# motorplank.net
KiCad netlist of a schematic drawn in EAGLE
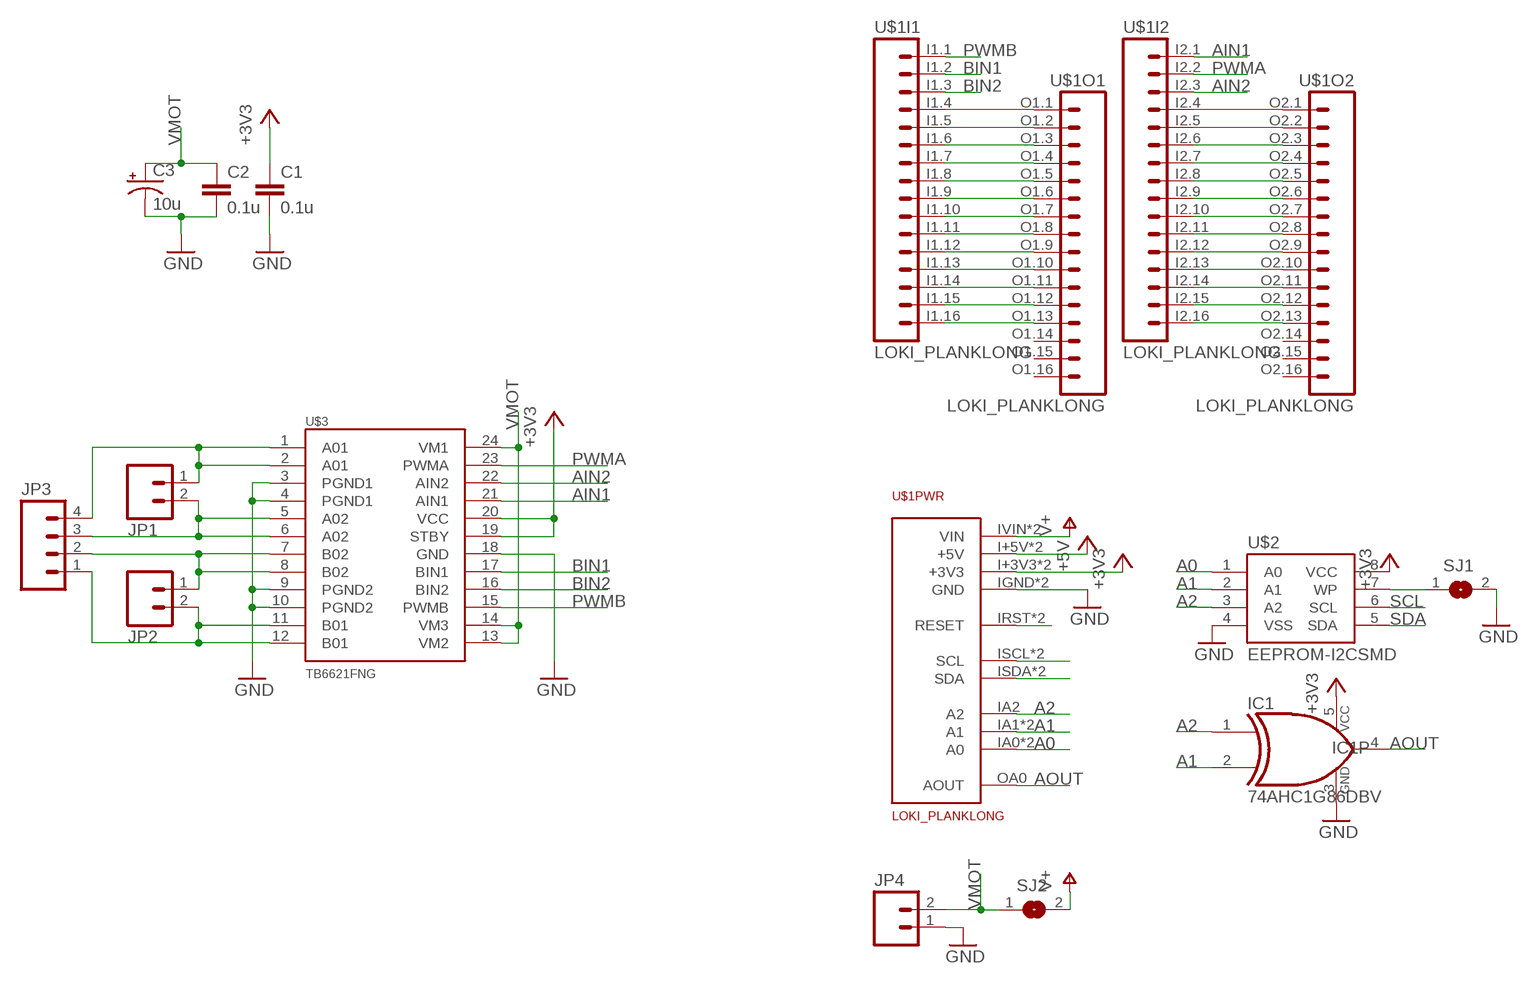
[diagram p0: schematic, sheet 1]

(export (version "E")
  (design (tool "Eeschema 10.0.6"))
  (components
    (comp (ref "C1")
      (value "0.1u")
      (footprint "eagle-import:0603-CAP")
      (libsource (lib "eagle-import") (part "CAP0603-CAP"))
    )
    (comp (ref "C2")
      (value "0.1u")
      (footprint "eagle-import:0603-CAP")
      (libsource (lib "eagle-import") (part "CAP0603-CAP"))
    )
    (comp (ref "C3")
      (value "10u")
      (footprint "eagle-import:PANASONIC_C")
      (libsource (lib "eagle-import") (part "CAP_POLC"))
    )
    (comp (ref "IC1")
      (value "74AHC1G86DBV")
      (footprint "eagle-import:SOT23-5")
      (libsource (lib "eagle-import") (part "741G86DBVAHC"))
    )
    (comp (ref "JP1")
      (value "M023.5MM")
      (footprint "eagle-import:SCREWTERMINAL-3.5MM-2")
      (libsource (lib "eagle-import") (part "M023.5MM"))
    )
    (comp (ref "JP2")
      (value "M023.5MM")
      (footprint "eagle-import:SCREWTERMINAL-3.5MM-2")
      (libsource (lib "eagle-import") (part "M023.5MM"))
    )
    (comp (ref "JP3")
      (value "M04PTH")
      (footprint "eagle-import:1X04")
      (libsource (lib "eagle-import") (part "M04PTH"))
    )
    (comp (ref "JP4")
      (value "M023.5MM")
      (footprint "eagle-import:SCREWTERMINAL-3.5MM-2")
      (libsource (lib "eagle-import") (part "M023.5MM"))
    )
    (comp (ref "SJ1") (value "SJ") (footprint "eagle-import:SJ") (libsource (lib "eagle-import") (part "SJ")))
    (comp (ref "SJ2") (value "SJ") (footprint "eagle-import:SJ") (libsource (lib "eagle-import") (part "SJ")))
    (comp (ref "U$1")
      (value "LOKI_PLANKLONG")
      (footprint "eagle-import:PLANK_LONG")
      (libsource (lib "eagle-import") (part "LOKI_PLANKLONG"))
    )
    (comp (ref "U$2")
      (value "EEPROM-I2CSMD")
      (footprint "eagle-import:SO08")
      (libsource (lib "eagle-import") (part "EEPROM-I2CSMD"))
    )
    (comp (ref "U$3")
      (value "TB6621FNG")
      (footprint "eagle-import:SSOP24")
      (libsource (lib "eagle-import") (part "TB6621FNG"))
    )
  )
  (nets
    (net (code "1") (name "+3V3") (class "Default")
      (node (ref "C1") (pin "1") (pinfunction "1_1") (pintype "passive"))
      (node (ref "IC1") (pin "5") (pinfunction "VCC_5") (pintype "power_in"))
      (node (ref "U$1") (pin "I+3V3") (pinfunction "+3V3_I+3V3") (pintype "power_in"))
      (node (ref "U$1") (pin "O+3V3") (pinfunction "+3V3_O+3V3") (pintype "power_in"))
      (node (ref "U$2") (pin "8") (pinfunction "VCC_8") (pintype "power_in"))
      (node (ref "U$3") (pin "19") (pinfunction "STBY_19") (pintype "bidirectional"))
      (node (ref "U$3") (pin "20") (pinfunction "VCC_20") (pintype "bidirectional"))
    )
    (net (code "2") (name "+5V") (class "Default")
      (node (ref "U$1") (pin "I+5V") (pinfunction "+5V_I+5V") (pintype "power_in"))
      (node (ref "U$1") (pin "O+5V") (pinfunction "+5V_O+5V") (pintype "power_in"))
    )
    (net (code "3") (name "/A0") (class "Default")
      (node (ref "U$1") (pin "IA0") (pinfunction "A0_IA0") (pintype "output"))
      (node (ref "U$1") (pin "OA1") (pinfunction "A0_OA1") (pintype "output"))
      (node (ref "U$2") (pin "1") (pinfunction "A0_1") (pintype "bidirectional"))
    )
    (net (code "4") (name "/A1") (class "Default")
      (node (ref "IC1") (pin "2") (pinfunction "I1_2") (pintype "input"))
      (node (ref "U$1") (pin "IA1") (pinfunction "A1_IA1") (pintype "output"))
      (node (ref "U$1") (pin "OA2") (pinfunction "A1_OA2") (pintype "output"))
      (node (ref "U$2") (pin "2") (pinfunction "A1_2") (pintype "bidirectional"))
    )
    (net (code "5") (name "/A2") (class "Default")
      (node (ref "IC1") (pin "1") (pinfunction "I0_1") (pintype "input"))
      (node (ref "U$1") (pin "IA2") (pinfunction "A2_IA2") (pintype "output"))
      (node (ref "U$2") (pin "3") (pinfunction "A2_3") (pintype "bidirectional"))
    )
    (net (code "6") (name "/AIN1") (class "Default")
      (node (ref "U$1") (pin "I2.1") (pinfunction "1_I2.1") (pintype "passive"))
      (node (ref "U$3") (pin "21") (pinfunction "AIN1_21") (pintype "bidirectional"))
    )
    (net (code "7") (name "/AIN2") (class "Default")
      (node (ref "U$1") (pin "I2.3") (pinfunction "3_I2.3") (pintype "passive"))
      (node (ref "U$3") (pin "22") (pinfunction "AIN2_22") (pintype "bidirectional"))
    )
    (net (code "8") (name "/AOUT") (class "Default")
      (node (ref "IC1") (pin "4") (pinfunction "O_4") (pintype "output"))
      (node (ref "U$1") (pin "OA0") (pinfunction "AOUT_OA0") (pintype "input"))
    )
    (net (code "9") (name "/BIN1") (class "Default")
      (node (ref "U$1") (pin "I1.2") (pinfunction "2_I1.2") (pintype "passive"))
      (node (ref "U$3") (pin "17") (pinfunction "BIN1_17") (pintype "bidirectional"))
    )
    (net (code "10") (name "/BIN2") (class "Default")
      (node (ref "U$1") (pin "I1.3") (pinfunction "3_I1.3") (pintype "passive"))
      (node (ref "U$3") (pin "16") (pinfunction "BIN2_16") (pintype "bidirectional"))
    )
    (net (code "11") (name "/PWMA") (class "Default")
      (node (ref "U$1") (pin "I2.2") (pinfunction "2_I2.2") (pintype "passive"))
      (node (ref "U$3") (pin "23") (pinfunction "PWMA_23") (pintype "bidirectional"))
    )
    (net (code "12") (name "/PWMB") (class "Default")
      (node (ref "U$1") (pin "I1.1") (pinfunction "1_I1.1") (pintype "passive"))
      (node (ref "U$3") (pin "15") (pinfunction "PWMB_15") (pintype "bidirectional"))
    )
    (net (code "13") (name "/SCL") (class "Default")
      (node (ref "U$1") (pin "ISCL") (pinfunction "SCL_ISCL") (pintype "bidirectional"))
      (node (ref "U$1") (pin "OSCL") (pinfunction "SCL_OSCL") (pintype "bidirectional"))
      (node (ref "U$2") (pin "6") (pinfunction "SCL_6") (pintype "bidirectional"))
    )
    (net (code "14") (name "/SDA") (class "Default")
      (node (ref "U$1") (pin "ISDA") (pinfunction "SDA_ISDA") (pintype "bidirectional"))
      (node (ref "U$1") (pin "OSDA") (pinfunction "SDA_OSDA") (pintype "bidirectional"))
      (node (ref "U$2") (pin "5") (pinfunction "SDA_5") (pintype "bidirectional"))
    )
    (net (code "15") (name "/VMOT") (class "Default")
      (node (ref "C2") (pin "1") (pinfunction "1_1") (pintype "passive"))
      (node (ref "C3") (pin "+") (pinfunction "+_+") (pintype "passive"))
      (node (ref "JP4") (pin "2") (pinfunction "2_2") (pintype "passive"))
      (node (ref "SJ2") (pin "1") (pinfunction "1_1") (pintype "passive"))
      (node (ref "U$3") (pin "13") (pinfunction "VM2_13") (pintype "bidirectional"))
      (node (ref "U$3") (pin "14") (pinfunction "VM3_14") (pintype "bidirectional"))
      (node (ref "U$3") (pin "24") (pinfunction "VM1_24") (pintype "bidirectional"))
    )
    (net (code "16") (name "GND") (class "Default")
      (node (ref "C1") (pin "2") (pinfunction "2_2") (pintype "passive"))
      (node (ref "C2") (pin "2") (pinfunction "2_2") (pintype "passive"))
      (node (ref "C3") (pin "-") (pinfunction "-_-") (pintype "passive"))
      (node (ref "IC1") (pin "3") (pinfunction "GND_3") (pintype "power_in"))
      (node (ref "JP4") (pin "1") (pinfunction "1_1") (pintype "passive"))
      (node (ref "SJ1") (pin "2") (pinfunction "2_2") (pintype "passive"))
      (node (ref "U$1") (pin "IGND") (pinfunction "GND_IGND") (pintype "power_in"))
      (node (ref "U$1") (pin "OGND") (pinfunction "GND_OGND") (pintype "power_in"))
      (node (ref "U$2") (pin "4") (pinfunction "VSS_4") (pintype "power_in"))
      (node (ref "U$3") (pin "10") (pinfunction "PGND2_10") (pintype "bidirectional"))
      (node (ref "U$3") (pin "18") (pinfunction "GND_18") (pintype "bidirectional"))
      (node (ref "U$3") (pin "3") (pinfunction "PGND1_3") (pintype "bidirectional"))
      (node (ref "U$3") (pin "4") (pinfunction "PGND1_4") (pintype "bidirectional"))
      (node (ref "U$3") (pin "9") (pinfunction "PGND2_9") (pintype "bidirectional"))
    )
    (net (code "17") (name "Net-(JP1-Pad1)") (class "Default")
      (node (ref "JP1") (pin "1") (pinfunction "1_1") (pintype "passive"))
      (node (ref "JP3") (pin "4") (pinfunction "4_4") (pintype "passive"))
      (node (ref "U$3") (pin "1") (pinfunction "A01_1") (pintype "bidirectional"))
      (node (ref "U$3") (pin "2") (pinfunction "A01_2") (pintype "bidirectional"))
    )
    (net (code "18") (name "Net-(JP1-Pad2)") (class "Default")
      (node (ref "JP1") (pin "2") (pinfunction "2_2") (pintype "passive"))
      (node (ref "JP3") (pin "3") (pinfunction "3_3") (pintype "passive"))
      (node (ref "U$3") (pin "5") (pinfunction "A02_5") (pintype "bidirectional"))
      (node (ref "U$3") (pin "6") (pinfunction "A02_6") (pintype "bidirectional"))
    )
    (net (code "19") (name "Net-(JP2-Pad1)") (class "Default")
      (node (ref "JP2") (pin "1") (pinfunction "1_1") (pintype "passive"))
      (node (ref "JP3") (pin "2") (pinfunction "2_2") (pintype "passive"))
      (node (ref "U$3") (pin "7") (pinfunction "B02_7") (pintype "bidirectional"))
      (node (ref "U$3") (pin "8") (pinfunction "B02_8") (pintype "bidirectional"))
    )
    (net (code "20") (name "Net-(JP2-Pad2)") (class "Default")
      (node (ref "JP2") (pin "2") (pinfunction "2_2") (pintype "passive"))
      (node (ref "JP3") (pin "1") (pinfunction "1_1") (pintype "passive"))
      (node (ref "U$3") (pin "11") (pinfunction "B01_11") (pintype "bidirectional"))
      (node (ref "U$3") (pin "12") (pinfunction "B01_12") (pintype "bidirectional"))
    )
    (net (code "21") (name "Net-(U$1A-4)") (class "Default")
      (node (ref "U$1") (pin "I1.4") (pinfunction "4_I1.4") (pintype "passive"))
      (node (ref "U$1") (pin "O1.1") (pinfunction "1_O1.1") (pintype "passive"))
    )
    (net (code "22") (name "Net-(U$1A-5)") (class "Default")
      (node (ref "U$1") (pin "I1.5") (pinfunction "5_I1.5") (pintype "passive"))
      (node (ref "U$1") (pin "O1.2") (pinfunction "2_O1.2") (pintype "passive"))
    )
    (net (code "23") (name "Net-(U$1A-6)") (class "Default")
      (node (ref "U$1") (pin "I1.6") (pinfunction "6_I1.6") (pintype "passive"))
      (node (ref "U$1") (pin "O1.3") (pinfunction "3_O1.3") (pintype "passive"))
    )
    (net (code "24") (name "Net-(U$1A-7)") (class "Default")
      (node (ref "U$1") (pin "I1.7") (pinfunction "7_I1.7") (pintype "passive"))
      (node (ref "U$1") (pin "O1.4") (pinfunction "4_O1.4") (pintype "passive"))
    )
    (net (code "25") (name "Net-(U$1A-8)") (class "Default")
      (node (ref "U$1") (pin "I1.8") (pinfunction "8_I1.8") (pintype "passive"))
      (node (ref "U$1") (pin "O1.5") (pinfunction "5_O1.5") (pintype "passive"))
    )
    (net (code "26") (name "Net-(U$1A-9)") (class "Default")
      (node (ref "U$1") (pin "I1.9") (pinfunction "9_I1.9") (pintype "passive"))
      (node (ref "U$1") (pin "O1.6") (pinfunction "6_O1.6") (pintype "passive"))
    )
    (net (code "27") (name "Net-(U$1A-10)") (class "Default")
      (node (ref "U$1") (pin "I1.10") (pinfunction "10_I1.10") (pintype "passive"))
      (node (ref "U$1") (pin "O1.7") (pinfunction "7_O1.7") (pintype "passive"))
    )
    (net (code "28") (name "Net-(U$1A-11)") (class "Default")
      (node (ref "U$1") (pin "I1.11") (pinfunction "11_I1.11") (pintype "passive"))
      (node (ref "U$1") (pin "O1.8") (pinfunction "8_O1.8") (pintype "passive"))
    )
    (net (code "29") (name "Net-(U$1A-12)") (class "Default")
      (node (ref "U$1") (pin "I1.12") (pinfunction "12_I1.12") (pintype "passive"))
      (node (ref "U$1") (pin "O1.9") (pinfunction "9_O1.9") (pintype "passive"))
    )
    (net (code "30") (name "Net-(U$1A-13)") (class "Default")
      (node (ref "U$1") (pin "I1.13") (pinfunction "13_I1.13") (pintype "passive"))
      (node (ref "U$1") (pin "O1.10") (pinfunction "10_O1.10") (pintype "passive"))
    )
    (net (code "31") (name "Net-(U$1A-14)") (class "Default")
      (node (ref "U$1") (pin "I1.14") (pinfunction "14_I1.14") (pintype "passive"))
      (node (ref "U$1") (pin "O1.11") (pinfunction "11_O1.11") (pintype "passive"))
    )
    (net (code "32") (name "Net-(U$1A-15)") (class "Default")
      (node (ref "U$1") (pin "I1.15") (pinfunction "15_I1.15") (pintype "passive"))
      (node (ref "U$1") (pin "O1.12") (pinfunction "12_O1.12") (pintype "passive"))
    )
    (net (code "33") (name "Net-(U$1A-16)") (class "Default")
      (node (ref "U$1") (pin "I1.16") (pinfunction "16_I1.16") (pintype "passive"))
      (node (ref "U$1") (pin "O1.13") (pinfunction "13_O1.13") (pintype "passive"))
    )
    (net (code "34") (name "Net-(U$1B-4)") (class "Default")
      (node (ref "U$1") (pin "I2.4") (pinfunction "4_I2.4") (pintype "passive"))
      (node (ref "U$1") (pin "O2.1") (pinfunction "1_O2.1") (pintype "passive"))
    )
    (net (code "35") (name "Net-(U$1B-5)") (class "Default")
      (node (ref "U$1") (pin "I2.5") (pinfunction "5_I2.5") (pintype "passive"))
      (node (ref "U$1") (pin "O2.2") (pinfunction "2_O2.2") (pintype "passive"))
    )
    (net (code "36") (name "Net-(U$1B-6)") (class "Default")
      (node (ref "U$1") (pin "I2.6") (pinfunction "6_I2.6") (pintype "passive"))
      (node (ref "U$1") (pin "O2.3") (pinfunction "3_O2.3") (pintype "passive"))
    )
    (net (code "37") (name "Net-(U$1B-7)") (class "Default")
      (node (ref "U$1") (pin "I2.7") (pinfunction "7_I2.7") (pintype "passive"))
      (node (ref "U$1") (pin "O2.4") (pinfunction "4_O2.4") (pintype "passive"))
    )
    (net (code "38") (name "Net-(U$1B-8)") (class "Default")
      (node (ref "U$1") (pin "I2.8") (pinfunction "8_I2.8") (pintype "passive"))
      (node (ref "U$1") (pin "O2.5") (pinfunction "5_O2.5") (pintype "passive"))
    )
    (net (code "39") (name "Net-(U$1B-9)") (class "Default")
      (node (ref "U$1") (pin "I2.9") (pinfunction "9_I2.9") (pintype "passive"))
      (node (ref "U$1") (pin "O2.6") (pinfunction "6_O2.6") (pintype "passive"))
    )
    (net (code "40") (name "Net-(U$1B-10)") (class "Default")
      (node (ref "U$1") (pin "I2.10") (pinfunction "10_I2.10") (pintype "passive"))
      (node (ref "U$1") (pin "O2.7") (pinfunction "7_O2.7") (pintype "passive"))
    )
    (net (code "41") (name "Net-(U$1B-11)") (class "Default")
      (node (ref "U$1") (pin "I2.11") (pinfunction "11_I2.11") (pintype "passive"))
      (node (ref "U$1") (pin "O2.8") (pinfunction "8_O2.8") (pintype "passive"))
    )
    (net (code "42") (name "Net-(U$1B-12)") (class "Default")
      (node (ref "U$1") (pin "I2.12") (pinfunction "12_I2.12") (pintype "passive"))
      (node (ref "U$1") (pin "O2.9") (pinfunction "9_O2.9") (pintype "passive"))
    )
    (net (code "43") (name "Net-(U$1B-13)") (class "Default")
      (node (ref "U$1") (pin "I2.13") (pinfunction "13_I2.13") (pintype "passive"))
      (node (ref "U$1") (pin "O2.10") (pinfunction "10_O2.10") (pintype "passive"))
    )
    (net (code "44") (name "Net-(U$1B-14)") (class "Default")
      (node (ref "U$1") (pin "I2.14") (pinfunction "14_I2.14") (pintype "passive"))
      (node (ref "U$1") (pin "O2.11") (pinfunction "11_O2.11") (pintype "passive"))
    )
    (net (code "45") (name "Net-(U$1B-15)") (class "Default")
      (node (ref "U$1") (pin "I2.15") (pinfunction "15_I2.15") (pintype "passive"))
      (node (ref "U$1") (pin "O2.12") (pinfunction "12_O2.12") (pintype "passive"))
    )
    (net (code "46") (name "Net-(U$1B-16)") (class "Default")
      (node (ref "U$1") (pin "I2.16") (pinfunction "16_I2.16") (pintype "passive"))
      (node (ref "U$1") (pin "O2.13") (pinfunction "13_O2.13") (pintype "passive"))
    )
    (net (code "47") (name "Net-(U$1E-RESET-PadIRST)") (class "Default")
      (node (ref "U$1") (pin "IRST") (pinfunction "RESET_IRST") (pintype "input"))
      (node (ref "U$1") (pin "ORST") (pinfunction "RESET_ORST") (pintype "input"))
    )
    (net (code "48") (name "Net-(U$2-WP)") (class "Default")
      (node (ref "SJ1") (pin "1") (pinfunction "1_1") (pintype "passive"))
      (node (ref "U$2") (pin "7") (pinfunction "WP_7") (pintype "bidirectional"))
    )
    (net (code "49") (name "V+") (class "Default")
      (node (ref "SJ2") (pin "2") (pinfunction "2_2") (pintype "passive"))
      (node (ref "U$1") (pin "IVIN") (pinfunction "VIN_IVIN") (pintype "power_in"))
      (node (ref "U$1") (pin "OVIN") (pinfunction "VIN_OVIN") (pintype "power_in"))
    )
    (net (code "50") (name "unconnected-(U$1C-14-PadO1.14)") (class "Default")
      (node (ref "U$1") (pin "O1.14") (pinfunction "14_O1.14") (pintype "passive"))
    )
    (net (code "51") (name "unconnected-(U$1C-15-PadO1.15)") (class "Default")
      (node (ref "U$1") (pin "O1.15") (pinfunction "15_O1.15") (pintype "passive"))
    )
    (net (code "52") (name "unconnected-(U$1C-16-PadO1.16)") (class "Default")
      (node (ref "U$1") (pin "O1.16") (pinfunction "16_O1.16") (pintype "passive"))
    )
    (net (code "53") (name "unconnected-(U$1D-14-PadO2.14)") (class "Default")
      (node (ref "U$1") (pin "O2.14") (pinfunction "14_O2.14") (pintype "passive"))
    )
    (net (code "54") (name "unconnected-(U$1D-15-PadO2.15)") (class "Default")
      (node (ref "U$1") (pin "O2.15") (pinfunction "15_O2.15") (pintype "passive"))
    )
    (net (code "55") (name "unconnected-(U$1D-16-PadO2.16)") (class "Default")
      (node (ref "U$1") (pin "O2.16") (pinfunction "16_O2.16") (pintype "passive"))
    )
  )
)
